# MainPCB.net
KiCad netlist of a schematic drawn in Altium Designer
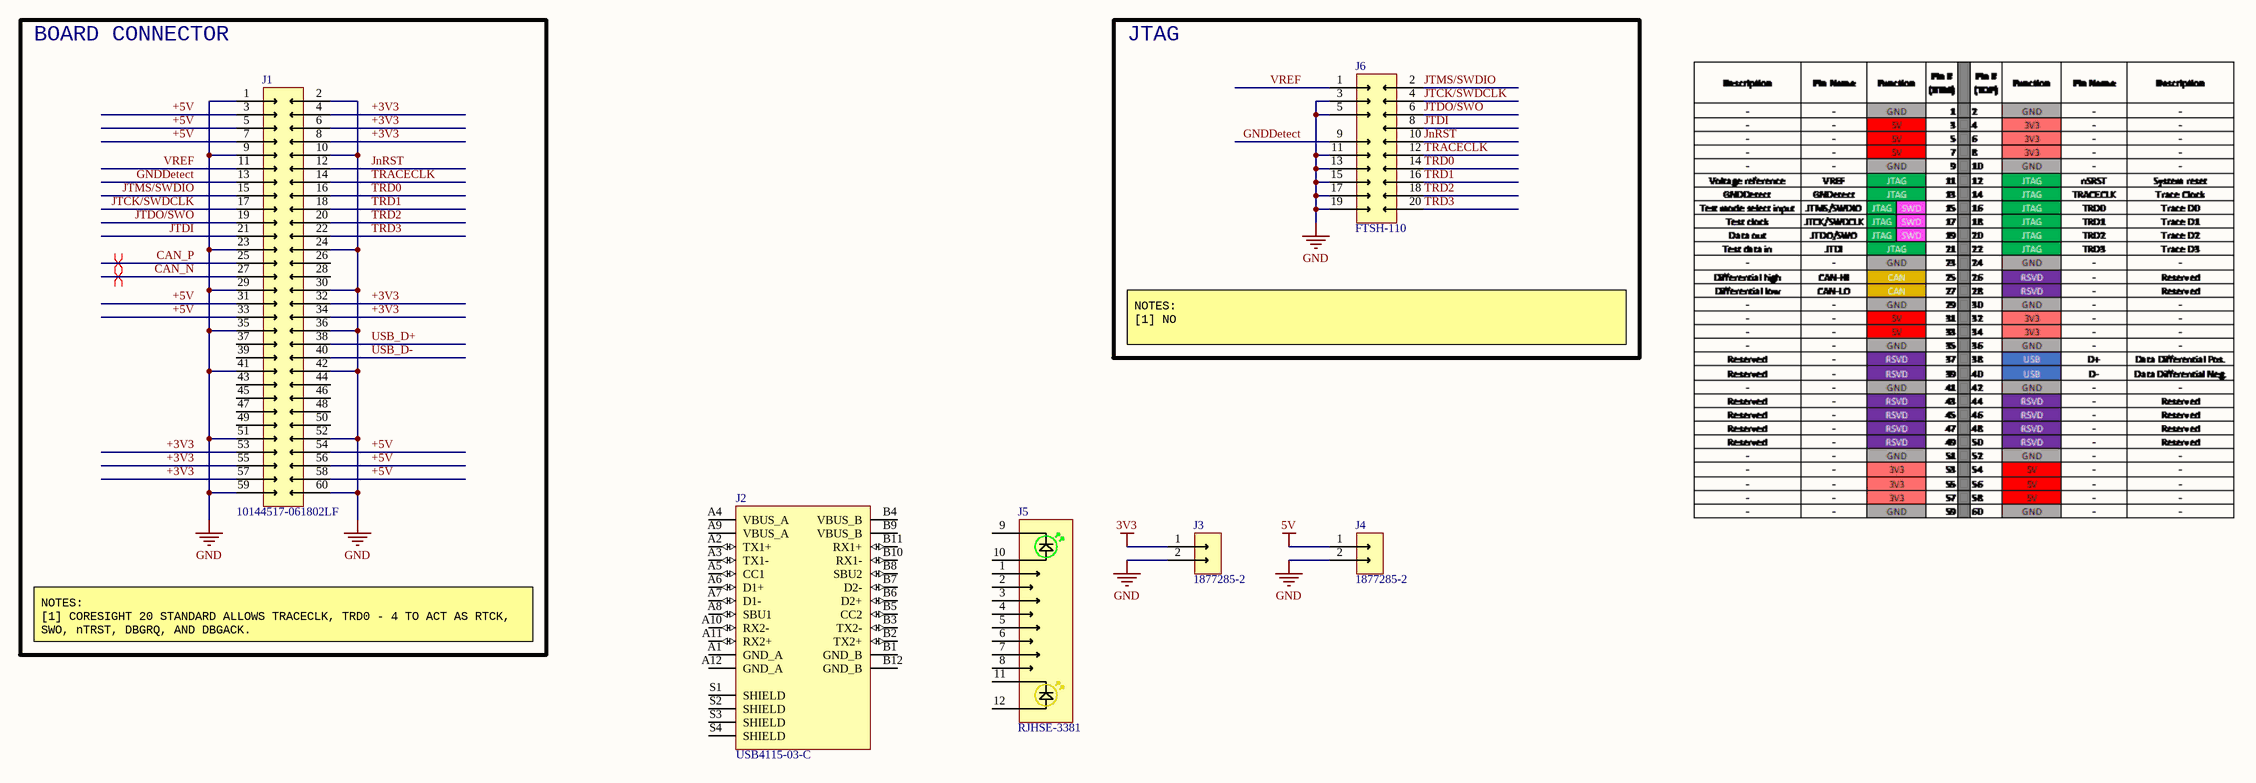
[diagram p0: MainPCB.SchDoc]

(export (version "E")
  (design (tool "Eeschema 10.0.6"))
  (components
    (comp (ref "J1")
      (value "10144517-061802LF")
      (footprint "AMPHENOL_10144517-061802LF")
      (description "CONN RCPT 60POS SMD GOLD")
      (libsource (lib "TGIS_Connectors") (part "10144517-061802LF"))
    )
    (comp (ref "J2")
      (value "USB4115-03-C")
      (footprint "GCT_USB4115-03-C_REVB2")
      (libsource (lib "TGIS_Connectors") (part "USB4115-03-C"))
    )
    (comp (ref "J3")
      (value "1877285-2")
      (footprint "TE_1877285-2")
      (libsource (lib "TGIS_Connectors") (part "1877285-2"))
    )
    (comp (ref "J4")
      (value "1877285-2")
      (footprint "TE_1877285-2")
      (libsource (lib "TGIS_Connectors") (part "1877285-2"))
    )
    (comp (ref "J5")
      (value "RJHSE-3381")
      (footprint "AMPHENOL_RJHSE3381")
      (description "Jack Modular Connector 8p8c (RJ45, Ethernet) Vertical Shielded")
      (libsource (lib "TGIS_Connectors") (part "RJHSE-3381"))
    )
    (comp (ref "J6")
      (value "FTSH-110")
      (footprint "SAMTEC_FTSH-110-01-L-DV-007")
      (description "Connector Header Surface Mount 20 position 0.050\" (1.27mm)")
      (libsource (lib "TGIS_Connectors") (part "FTSH-110-01-L-DV-007-K"))
    )
  )
  (nets
    (net (code "1") (name "/+3V3") (class "Default")
      (node (ref "J1") (pin "32") (pinfunction "32_32") (pintype "passive"))
      (node (ref "J1") (pin "34") (pinfunction "34_34") (pintype "passive"))
      (node (ref "J1") (pin "4") (pinfunction "4_4") (pintype "passive"))
      (node (ref "J1") (pin "53") (pinfunction "53_53") (pintype "passive"))
      (node (ref "J1") (pin "55") (pinfunction "55_55") (pintype "passive"))
      (node (ref "J1") (pin "57") (pinfunction "57_57") (pintype "passive"))
      (node (ref "J1") (pin "6") (pinfunction "6_6") (pintype "passive"))
      (node (ref "J1") (pin "8") (pinfunction "8_8") (pintype "passive"))
    )
    (net (code "2") (name "/+5V") (class "Default")
      (node (ref "J1") (pin "3") (pinfunction "3_3") (pintype "passive"))
      (node (ref "J1") (pin "31") (pinfunction "31_31") (pintype "passive"))
      (node (ref "J1") (pin "33") (pinfunction "33_33") (pintype "passive"))
      (node (ref "J1") (pin "5") (pinfunction "5_5") (pintype "passive"))
      (node (ref "J1") (pin "54") (pinfunction "54_54") (pintype "passive"))
      (node (ref "J1") (pin "56") (pinfunction "56_56") (pintype "passive"))
      (node (ref "J1") (pin "58") (pinfunction "58_58") (pintype "passive"))
      (node (ref "J1") (pin "7") (pinfunction "7_7") (pintype "passive"))
    )
    (net (code "3") (name "/CAN_N") (class "Default")
      (node (ref "J1") (pin "27") (pinfunction "27_27") (pintype "passive"))
    )
    (net (code "4") (name "/CAN_P") (class "Default")
      (node (ref "J1") (pin "25") (pinfunction "25_25") (pintype "passive"))
    )
    (net (code "5") (name "/GNDDetect") (class "Default")
      (node (ref "J1") (pin "13") (pinfunction "13_13") (pintype "passive"))
      (node (ref "J6") (pin "9") (pinfunction "9_9") (pintype "passive"))
    )
    (net (code "6") (name "/JTCK{slash}SWDCLK") (class "Default")
      (node (ref "J1") (pin "17") (pinfunction "17_17") (pintype "passive"))
      (node (ref "J6") (pin "4") (pinfunction "4_4") (pintype "passive"))
    )
    (net (code "7") (name "/JTDI") (class "Default")
      (node (ref "J1") (pin "21") (pinfunction "21_21") (pintype "passive"))
      (node (ref "J6") (pin "8") (pinfunction "8_8") (pintype "passive"))
    )
    (net (code "8") (name "/JTDO{slash}SWO") (class "Default")
      (node (ref "J1") (pin "19") (pinfunction "19_19") (pintype "passive"))
      (node (ref "J6") (pin "6") (pinfunction "6_6") (pintype "passive"))
    )
    (net (code "9") (name "/JTMS{slash}SWDIO") (class "Default")
      (node (ref "J1") (pin "15") (pinfunction "15_15") (pintype "passive"))
      (node (ref "J6") (pin "2") (pinfunction "2_2") (pintype "passive"))
    )
    (net (code "10") (name "/JnRST") (class "Default")
      (node (ref "J1") (pin "12") (pinfunction "12_12") (pintype "passive"))
      (node (ref "J6") (pin "10") (pinfunction "10_10") (pintype "passive"))
    )
    (net (code "11") (name "/TRACECLK") (class "Default")
      (node (ref "J1") (pin "14") (pinfunction "14_14") (pintype "passive"))
      (node (ref "J6") (pin "12") (pinfunction "12_12") (pintype "passive"))
    )
    (net (code "12") (name "/TRD0") (class "Default")
      (node (ref "J1") (pin "16") (pinfunction "16_16") (pintype "passive"))
      (node (ref "J6") (pin "14") (pinfunction "14_14") (pintype "passive"))
    )
    (net (code "13") (name "/TRD1") (class "Default")
      (node (ref "J1") (pin "18") (pinfunction "18_18") (pintype "passive"))
      (node (ref "J6") (pin "16") (pinfunction "16_16") (pintype "passive"))
    )
    (net (code "14") (name "/TRD2") (class "Default")
      (node (ref "J1") (pin "20") (pinfunction "20_20") (pintype "passive"))
      (node (ref "J6") (pin "18") (pinfunction "18_18") (pintype "passive"))
    )
    (net (code "15") (name "/TRD3") (class "Default")
      (node (ref "J1") (pin "22") (pinfunction "22_22") (pintype "passive"))
      (node (ref "J6") (pin "20") (pinfunction "20_20") (pintype "passive"))
    )
    (net (code "16") (name "/USB_D+") (class "Default")
      (node (ref "J1") (pin "38") (pinfunction "38_38") (pintype "passive"))
    )
    (net (code "17") (name "/USB_D-") (class "Default")
      (node (ref "J1") (pin "40") (pinfunction "40_40") (pintype "passive"))
    )
    (net (code "18") (name "/VREF") (class "Default")
      (node (ref "J1") (pin "11") (pinfunction "11_11") (pintype "passive"))
      (node (ref "J6") (pin "1") (pinfunction "1_1") (pintype "passive"))
    )
    (net (code "19") (name "3V3") (class "Default")
      (node (ref "J3") (pin "1") (pinfunction "1_1") (pintype "passive"))
    )
    (net (code "20") (name "5V") (class "Default")
      (node (ref "J4") (pin "1") (pinfunction "1_1") (pintype "passive"))
    )
    (net (code "21") (name "GND") (class "Default")
      (node (ref "J1") (pin "1") (pinfunction "1_1") (pintype "passive"))
      (node (ref "J1") (pin "10") (pinfunction "10_10") (pintype "passive"))
      (node (ref "J1") (pin "2") (pinfunction "2_2") (pintype "passive"))
      (node (ref "J1") (pin "23") (pinfunction "23_23") (pintype "passive"))
      (node (ref "J1") (pin "24") (pinfunction "24_24") (pintype "passive"))
      (node (ref "J1") (pin "29") (pinfunction "29_29") (pintype "passive"))
      (node (ref "J1") (pin "30") (pinfunction "30_30") (pintype "passive"))
      (node (ref "J1") (pin "35") (pinfunction "35_35") (pintype "passive"))
      (node (ref "J1") (pin "36") (pinfunction "36_36") (pintype "passive"))
      (node (ref "J1") (pin "41") (pinfunction "41_41") (pintype "passive"))
      (node (ref "J1") (pin "42") (pinfunction "42_42") (pintype "passive"))
      (node (ref "J1") (pin "51") (pinfunction "51_51") (pintype "passive"))
      (node (ref "J1") (pin "52") (pinfunction "52_52") (pintype "passive"))
      (node (ref "J1") (pin "59") (pinfunction "59_59") (pintype "passive"))
      (node (ref "J1") (pin "60") (pinfunction "60_60") (pintype "passive"))
      (node (ref "J1") (pin "9") (pinfunction "9_9") (pintype "passive"))
      (node (ref "J3") (pin "2") (pinfunction "2_2") (pintype "passive"))
      (node (ref "J4") (pin "2") (pinfunction "2_2") (pintype "passive"))
      (node (ref "J6") (pin "11") (pinfunction "11_11") (pintype "passive"))
      (node (ref "J6") (pin "13") (pinfunction "13_13") (pintype "passive"))
      (node (ref "J6") (pin "15") (pinfunction "15_15") (pintype "passive"))
      (node (ref "J6") (pin "17") (pinfunction "17_17") (pintype "passive"))
      (node (ref "J6") (pin "19") (pinfunction "19_19") (pintype "passive"))
      (node (ref "J6") (pin "3") (pinfunction "3_3") (pintype "passive"))
      (node (ref "J6") (pin "5") (pinfunction "5_5") (pintype "passive"))
    )
    (net (code "22") (name "unconnected-(J1-Pad26)") (class "Default")
      (node (ref "J1") (pin "26") (pinfunction "26_26") (pintype "passive"))
    )
    (net (code "23") (name "unconnected-(J1-Pad28)") (class "Default")
      (node (ref "J1") (pin "28") (pinfunction "28_28") (pintype "passive"))
    )
    (net (code "24") (name "unconnected-(J1-Pad37)") (class "Default")
      (node (ref "J1") (pin "37") (pinfunction "37_37") (pintype "passive"))
    )
    (net (code "25") (name "unconnected-(J1-Pad39)") (class "Default")
      (node (ref "J1") (pin "39") (pinfunction "39_39") (pintype "passive"))
    )
    (net (code "26") (name "unconnected-(J1-Pad43)") (class "Default")
      (node (ref "J1") (pin "43") (pinfunction "43_43") (pintype "passive"))
    )
    (net (code "27") (name "unconnected-(J1-Pad44)") (class "Default")
      (node (ref "J1") (pin "44") (pinfunction "44_44") (pintype "passive"))
    )
    (net (code "28") (name "unconnected-(J1-Pad45)") (class "Default")
      (node (ref "J1") (pin "45") (pinfunction "45_45") (pintype "passive"))
    )
    (net (code "29") (name "unconnected-(J1-Pad46)") (class "Default")
      (node (ref "J1") (pin "46") (pinfunction "46_46") (pintype "passive"))
    )
    (net (code "30") (name "unconnected-(J1-Pad47)") (class "Default")
      (node (ref "J1") (pin "47") (pinfunction "47_47") (pintype "passive"))
    )
    (net (code "31") (name "unconnected-(J1-Pad48)") (class "Default")
      (node (ref "J1") (pin "48") (pinfunction "48_48") (pintype "passive"))
    )
    (net (code "32") (name "unconnected-(J1-Pad49)") (class "Default")
      (node (ref "J1") (pin "49") (pinfunction "49_49") (pintype "passive"))
    )
    (net (code "33") (name "unconnected-(J1-Pad50)") (class "Default")
      (node (ref "J1") (pin "50") (pinfunction "50_50") (pintype "passive"))
    )
    (net (code "34") (name "unconnected-(J2-CC1-PadA5)") (class "Default")
      (node (ref "J2") (pin "A5") (pinfunction "CC1_A5") (pintype "bidirectional"))
    )
    (net (code "35") (name "unconnected-(J2-CC2-PadB5)") (class "Default")
      (node (ref "J2") (pin "B5") (pinfunction "CC2_B5") (pintype "bidirectional"))
    )
    (net (code "36") (name "unconnected-(J2-D1+-PadA6)") (class "Default")
      (node (ref "J2") (pin "A6") (pinfunction "D1+_A6") (pintype "bidirectional"))
    )
    (net (code "37") (name "unconnected-(J2-D1--PadA7)") (class "Default")
      (node (ref "J2") (pin "A7") (pinfunction "D1-_A7") (pintype "bidirectional"))
    )
    (net (code "38") (name "unconnected-(J2-D2+-PadB6)") (class "Default")
      (node (ref "J2") (pin "B6") (pinfunction "D2+_B6") (pintype "bidirectional"))
    )
    (net (code "39") (name "unconnected-(J2-D2--PadB7)") (class "Default")
      (node (ref "J2") (pin "B7") (pinfunction "D2-_B7") (pintype "bidirectional"))
    )
    (net (code "40") (name "unconnected-(J2-GND_A-PadA1)") (class "Default")
      (node (ref "J2") (pin "A1") (pinfunction "GND_A_A1") (pintype "power_in"))
    )
    (net (code "41") (name "unconnected-(J2-GND_A-PadA12)") (class "Default")
      (node (ref "J2") (pin "A12") (pinfunction "GND_A_A12") (pintype "power_in"))
    )
    (net (code "42") (name "unconnected-(J2-GND_B-PadB1)") (class "Default")
      (node (ref "J2") (pin "B1") (pinfunction "GND_B_B1") (pintype "power_in"))
    )
    (net (code "43") (name "unconnected-(J2-GND_B-PadB12)") (class "Default")
      (node (ref "J2") (pin "B12") (pinfunction "GND_B_B12") (pintype "power_in"))
    )
    (net (code "44") (name "unconnected-(J2-RX1+-PadB11)") (class "Default")
      (node (ref "J2") (pin "B11") (pinfunction "RX1+_B11") (pintype "bidirectional"))
    )
    (net (code "45") (name "unconnected-(J2-RX1--PadB10)") (class "Default")
      (node (ref "J2") (pin "B10") (pinfunction "RX1-_B10") (pintype "bidirectional"))
    )
    (net (code "46") (name "unconnected-(J2-RX2+-PadA11)") (class "Default")
      (node (ref "J2") (pin "A11") (pinfunction "RX2+_A11") (pintype "bidirectional"))
    )
    (net (code "47") (name "unconnected-(J2-RX2--PadA10)") (class "Default")
      (node (ref "J2") (pin "A10") (pinfunction "RX2-_A10") (pintype "bidirectional"))
    )
    (net (code "48") (name "unconnected-(J2-SBU1-PadA8)") (class "Default")
      (node (ref "J2") (pin "A8") (pinfunction "SBU1_A8") (pintype "bidirectional"))
    )
    (net (code "49") (name "unconnected-(J2-SBU2-PadB8)") (class "Default")
      (node (ref "J2") (pin "B8") (pinfunction "SBU2_B8") (pintype "bidirectional"))
    )
    (net (code "50") (name "unconnected-(J2-SHIELD-PadS1)") (class "Default")
      (node (ref "J2") (pin "S1") (pinfunction "SHIELD_S1") (pintype "passive"))
    )
    (net (code "51") (name "unconnected-(J2-SHIELD-PadS2)") (class "Default")
      (node (ref "J2") (pin "S2") (pinfunction "SHIELD_S2") (pintype "passive"))
    )
    (net (code "52") (name "unconnected-(J2-SHIELD-PadS3)") (class "Default")
      (node (ref "J2") (pin "S3") (pinfunction "SHIELD_S3") (pintype "passive"))
    )
    (net (code "53") (name "unconnected-(J2-SHIELD-PadS4)") (class "Default")
      (node (ref "J2") (pin "S4") (pinfunction "SHIELD_S4") (pintype "passive"))
    )
    (net (code "54") (name "unconnected-(J2-TX1+-PadA2)") (class "Default")
      (node (ref "J2") (pin "A2") (pinfunction "TX1+_A2") (pintype "bidirectional"))
    )
    (net (code "55") (name "unconnected-(J2-TX1--PadA3)") (class "Default")
      (node (ref "J2") (pin "A3") (pinfunction "TX1-_A3") (pintype "bidirectional"))
    )
    (net (code "56") (name "unconnected-(J2-TX2+-PadB2)") (class "Default")
      (node (ref "J2") (pin "B2") (pinfunction "TX2+_B2") (pintype "bidirectional"))
    )
    (net (code "57") (name "unconnected-(J2-TX2--PadB3)") (class "Default")
      (node (ref "J2") (pin "B3") (pinfunction "TX2-_B3") (pintype "bidirectional"))
    )
    (net (code "58") (name "unconnected-(J2-VBUS_A-PadA4)") (class "Default")
      (node (ref "J2") (pin "A4") (pinfunction "VBUS_A_A4") (pintype "power_in"))
    )
    (net (code "59") (name "unconnected-(J2-VBUS_A-PadA9)") (class "Default")
      (node (ref "J2") (pin "A9") (pinfunction "VBUS_A_A9") (pintype "power_in"))
    )
    (net (code "60") (name "unconnected-(J2-VBUS_B-PadB4)") (class "Default")
      (node (ref "J2") (pin "B4") (pinfunction "VBUS_B_B4") (pintype "power_in"))
    )
    (net (code "61") (name "unconnected-(J2-VBUS_B-PadB9)") (class "Default")
      (node (ref "J2") (pin "B9") (pinfunction "VBUS_B_B9") (pintype "power_in"))
    )
    (net (code "62") (name "unconnected-(J5-G+-Pad10)") (class "Default")
      (node (ref "J5") (pin "10") (pinfunction "G+_10") (pintype "passive"))
    )
    (net (code "63") (name "unconnected-(J5-G--Pad9)") (class "Default")
      (node (ref "J5") (pin "9") (pinfunction "G-_9") (pintype "passive"))
    )
    (net (code "64") (name "unconnected-(J5-Pad1)") (class "Default")
      (node (ref "J5") (pin "1") (pintype "passive"))
    )
    (net (code "65") (name "unconnected-(J5-Pad2)") (class "Default")
      (node (ref "J5") (pin "2") (pintype "passive"))
    )
    (net (code "66") (name "unconnected-(J5-Pad3)") (class "Default")
      (node (ref "J5") (pin "3") (pintype "passive"))
    )
    (net (code "67") (name "unconnected-(J5-Pad4)") (class "Default")
      (node (ref "J5") (pin "4") (pintype "passive"))
    )
    (net (code "68") (name "unconnected-(J5-Pad5)") (class "Default")
      (node (ref "J5") (pin "5") (pintype "passive"))
    )
    (net (code "69") (name "unconnected-(J5-Pad6)") (class "Default")
      (node (ref "J5") (pin "6") (pintype "passive"))
    )
    (net (code "70") (name "unconnected-(J5-Pad7)") (class "Default")
      (node (ref "J5") (pin "7") (pintype "passive"))
    )
    (net (code "71") (name "unconnected-(J5-Pad8)") (class "Default")
      (node (ref "J5") (pin "8") (pintype "passive"))
    )
    (net (code "72") (name "unconnected-(J5-Y+-Pad12)") (class "Default")
      (node (ref "J5") (pin "12") (pinfunction "Y+_12") (pintype "passive"))
    )
    (net (code "73") (name "unconnected-(J5-Y--Pad11)") (class "Default")
      (node (ref "J5") (pin "11") (pinfunction "Y-_11") (pintype "passive"))
    )
  )
)
